# whirlygig.net
KiCad netlist of a schematic drawn in Altium Designer
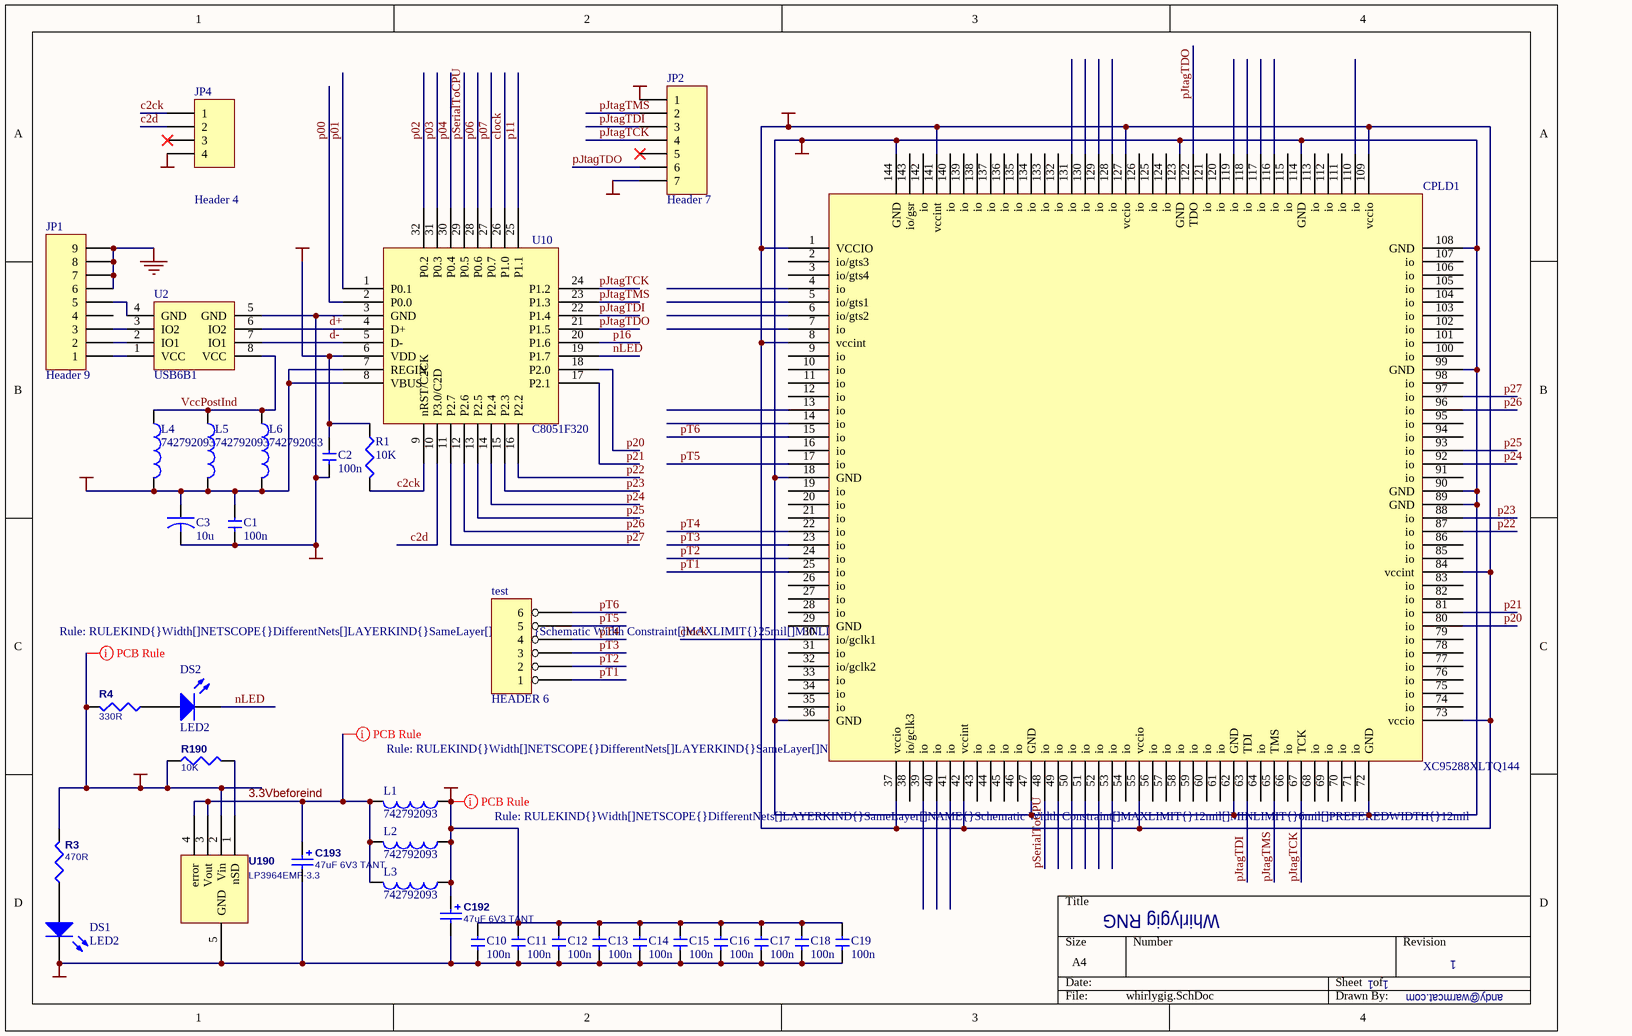
[diagram p0: whirlygig.SchDoc]

(export (version "E")
  (design (tool "Eeschema 10.0.6"))
  (components
    (comp (ref "C1") (value "100n") (footprint "C0603") (libsource (lib "*") (part "100N DISK")))
    (comp (ref "C2") (value "100n") (footprint "C0603") (libsource (lib "*") (part "100N DISK")))
    (comp (ref "C3") (value "10u") (footprint "TAJ-T") (libsource (lib "*") (part "1UF TANT")))
    (comp (ref "C10") (value "100n") (footprint "C0603") (libsource (lib "*") (part "100N DISK")))
    (comp (ref "C11") (value "100n") (footprint "C0603") (libsource (lib "*") (part "100N DISK")))
    (comp (ref "C12") (value "100n") (footprint "C0603") (libsource (lib "*") (part "100N DISK")))
    (comp (ref "C13") (value "100n") (footprint "C0603") (libsource (lib "*") (part "100N DISK")))
    (comp (ref "C14") (value "100n") (footprint "C0603") (libsource (lib "*") (part "100N DISK")))
    (comp (ref "C15") (value "100n") (footprint "C0603") (libsource (lib "*") (part "100N DISK")))
    (comp (ref "C16") (value "100n") (footprint "C0603") (libsource (lib "*") (part "100N DISK")))
    (comp (ref "C17") (value "100n") (footprint "C0603") (libsource (lib "*") (part "100N DISK")))
    (comp (ref "C18") (value "100n") (footprint "C0603") (libsource (lib "*") (part "100N DISK")))
    (comp (ref "C19") (value "100n") (footprint "C0603") (libsource (lib "*") (part "100N DISK")))
    (comp (ref "C192")
      (value "47uF 6V3 TANT")
      (footprint "TAJ-T")
      (description "Polarized Capacitor (Surface Mount)")
      (fields (field (name "PUBLISHER") "Altium Limited"))
      (libsource (lib "Miscellaneous Devices") (part "Cap Pol3"))
    )
    (comp (ref "C193")
      (value "47uF 6V3 TANT")
      (footprint "TAJ-T")
      (description "Polarized Capacitor (Surface Mount)")
      (fields (field (name "PUBLISHER") "Altium Limited"))
      (libsource (lib "Miscellaneous Devices") (part "Cap Pol3"))
    )
    (comp (ref "CPLD1")
      (value "XC95288XLTQ144")
      (footprint "TQFP144")
      (libsource (lib "*") (part "XC95288XLTQ144"))
    )
    (comp (ref "DS1")
      (value "LED2")
      (footprint "DSO-F2/D6.1")
      (description "Typical RED, GREEN, YELLOW, AMBER GaAs LED")
      (fields (field (name "PUBLISHER") "Altium Limited"))
      (libsource (lib "Miscellaneous Devices") (part "LED2"))
    )
    (comp (ref "DS2")
      (value "LED2")
      (footprint "DSO-F2/D6.1")
      (description "Typical RED, GREEN, YELLOW, AMBER GaAs LED")
      (fields (field (name "PUBLISHER") "Altium Limited"))
      (libsource (lib "Miscellaneous Devices") (part "LED2"))
    )
    (comp (ref "JP1")
      (value "Header 9")
      (footprint "USBSKT5MIN")
      (description "Header, 9-Pin")
      (fields (field (name "PUBLISHER") "Altium Limited"))
      (libsource (lib "Miscellaneous Connectors") (part "Header 9"))
    )
    (comp (ref "JP2")
      (value "Header 7")
      (footprint "HDR1X7")
      (description "Header, 7-Pin")
      (fields (field (name "PUBLISHER") "Altium Limited"))
      (libsource (lib "Miscellaneous Connectors") (part "Header 7"))
    )
    (comp (ref "JP4")
      (value "Header 4")
      (footprint "HDR1X4")
      (description "Header, 4-Pin")
      (fields (field (name "PUBLISHER") "Altium Limited"))
      (libsource (lib "Miscellaneous Connectors") (part "Header 4"))
    )
    (comp (ref "L1")
      (value "742792093")
      (footprint "C0805")
      (description "Inductor")
      (fields (field (name "PUBLISHER") "Altium Limited"))
      (libsource (lib "Miscellaneous Devices") (part "Inductor"))
    )
    (comp (ref "L2")
      (value "742792093")
      (footprint "C0805")
      (description "Inductor")
      (fields (field (name "PUBLISHER") "Altium Limited"))
      (libsource (lib "Miscellaneous Devices") (part "Inductor"))
    )
    (comp (ref "L3")
      (value "742792093")
      (footprint "C0805")
      (description "Inductor")
      (fields (field (name "PUBLISHER") "Altium Limited"))
      (libsource (lib "Miscellaneous Devices") (part "Inductor"))
    )
    (comp (ref "L4")
      (value "742792093")
      (footprint "C0805")
      (description "Inductor")
      (fields (field (name "PUBLISHER") "Altium Limited"))
      (libsource (lib "Miscellaneous Devices") (part "Inductor"))
    )
    (comp (ref "L5")
      (value "742792093")
      (footprint "C0805")
      (description "Inductor")
      (fields (field (name "PUBLISHER") "Altium Limited"))
      (libsource (lib "Miscellaneous Devices") (part "Inductor"))
    )
    (comp (ref "L6")
      (value "742792093")
      (footprint "C0805")
      (description "Inductor")
      (fields (field (name "PUBLISHER") "Altium Limited"))
      (libsource (lib "Miscellaneous Devices") (part "Inductor"))
    )
    (comp (ref "R1")
      (value "10K")
      (footprint "R0603")
      (description "Resistor")
      (libsource (lib "*") (part "100K"))
    )
    (comp (ref "R3")
      (value "470R")
      (footprint "R0603")
      (description "Resistor")
      (fields (field (name "PUBLISHER") "Altium Limited"))
      (libsource (lib "") (part "Res3_1"))
    )
    (comp (ref "R4")
      (value "330R")
      (footprint "R0603")
      (description "Resistor")
      (fields (field (name "PUBLISHER") "Altium Limited"))
      (libsource (lib "linuxboard_1") (part "Res3"))
    )
    (comp (ref "R190")
      (value "10K")
      (footprint "R0603")
      (description "Resistor")
      (fields (field (name "PUBLISHER") "Altium Limited"))
      (libsource (lib "linuxboard_1") (part "Res3"))
    )
    (comp (ref "test") (value "HEADER 6") (footprint "HDR1X6") (libsource (lib "*") (part "HEADER 6")))
    (comp (ref "U2")
      (value "USB6B1")
      (footprint "SOP8USB")
      (description "USB Protection Diodes")
      (libsource (lib "*") (part "USB6B1"))
    )
    (comp (ref "U10")
      (value "C8051F320")
      (footprint "LQFP32")
      (description "Cygnal USB flash chip")
      (libsource (lib "*") (part "Component_3"))
    )
    (comp (ref "U190") (value "LP3964EMP-3.3") (footprint "SOT-223-5") (libsource (lib "*") (part "LP3964")))
  )
  (nets
    (net (code "1") (name "/3.3Vbeforeind") (class "Default")
      (node (ref "C193") (pin "1") (pinfunction "1_1") (pintype "passive"))
      (node (ref "L1") (pin "2") (pinfunction "2_2") (pintype "passive"))
      (node (ref "L2") (pin "2") (pinfunction "2_2") (pintype "passive"))
      (node (ref "L3") (pin "2") (pinfunction "2_2") (pintype "passive"))
      (node (ref "U190") (pin "3") (pinfunction "Vout_3") (pintype "passive"))
      (node (ref "U190") (pin "4") (pinfunction "error_4") (pintype "passive"))
    )
    (net (code "2") (name "/VccPostInd") (class "Default")
      (node (ref "L4") (pin "1") (pinfunction "1_1") (pintype "passive"))
      (node (ref "L5") (pin "1") (pinfunction "1_1") (pintype "passive"))
      (node (ref "L6") (pin "1") (pinfunction "1_1") (pintype "passive"))
      (node (ref "U2") (pin "8") (pinfunction "VCC_8") (pintype "passive"))
    )
    (net (code "3") (name "/c2ck") (class "Default")
      (node (ref "JP4") (pin "1") (pinfunction "1_1") (pintype "passive"))
      (node (ref "R1") (pin "2") (pinfunction "2_2") (pintype "passive"))
      (node (ref "U10") (pin "9") (pinfunction "nRST/C2CK_9") (pintype "passive"))
    )
    (net (code "4") (name "/c2d") (class "Default")
      (node (ref "JP4") (pin "2") (pinfunction "2_2") (pintype "passive"))
      (node (ref "U10") (pin "10") (pinfunction "P3.0/C2D_10") (pintype "passive"))
    )
    (net (code "5") (name "/clock") (class "Default")
      (node (ref "CPLD1") (pin "30") (pinfunction "io/gclk1_30") (pintype "passive"))
      (node (ref "U10") (pin "26") (pinfunction "P1.0_26") (pintype "passive"))
    )
    (net (code "6") (name "/d+") (class "Default")
      (node (ref "U10") (pin "4") (pinfunction "D+_4") (pintype "passive"))
      (node (ref "U2") (pin "6") (pinfunction "IO2_6") (pintype "passive"))
    )
    (net (code "7") (name "/d-") (class "Default")
      (node (ref "U10") (pin "5") (pinfunction "D-_5") (pintype "passive"))
      (node (ref "U2") (pin "7") (pinfunction "IO1_7") (pintype "passive"))
    )
    (net (code "8") (name "/nLED") (class "Default")
      (node (ref "DS2") (pin "2") (pinfunction "K_2") (pintype "passive"))
      (node (ref "U10") (pin "19") (pinfunction "P1.7_19") (pintype "passive"))
    )
    (net (code "9") (name "/p00") (class "Default")
      (node (ref "U10") (pin "2") (pinfunction "P0.0_2") (pintype "passive"))
    )
    (net (code "10") (name "/p01") (class "Default")
      (node (ref "U10") (pin "1") (pinfunction "P0.1_1") (pintype "passive"))
    )
    (net (code "11") (name "/p02") (class "Default")
      (node (ref "U10") (pin "32") (pinfunction "P0.2_32") (pintype "passive"))
    )
    (net (code "12") (name "/p03") (class "Default")
      (node (ref "U10") (pin "31") (pinfunction "P0.3_31") (pintype "passive"))
    )
    (net (code "13") (name "/p04") (class "Default")
      (node (ref "U10") (pin "30") (pinfunction "P0.4_30") (pintype "passive"))
    )
    (net (code "14") (name "/p06") (class "Default")
      (node (ref "U10") (pin "28") (pinfunction "P0.6_28") (pintype "passive"))
    )
    (net (code "15") (name "/p07") (class "Default")
      (node (ref "U10") (pin "27") (pinfunction "P0.7_27") (pintype "passive"))
    )
    (net (code "16") (name "/p11") (class "Default")
      (node (ref "U10") (pin "25") (pinfunction "P1.1_25") (pintype "passive"))
    )
    (net (code "17") (name "/p16") (class "Default")
      (node (ref "U10") (pin "20") (pinfunction "P1.6_20") (pintype "passive"))
    )
    (net (code "18") (name "/p20") (class "Default")
      (node (ref "CPLD1") (pin "80") (pinfunction "io_80") (pintype "passive"))
      (node (ref "U10") (pin "18") (pinfunction "P2.0_18") (pintype "passive"))
    )
    (net (code "19") (name "/p21") (class "Default")
      (node (ref "CPLD1") (pin "81") (pinfunction "io_81") (pintype "passive"))
      (node (ref "U10") (pin "17") (pinfunction "P2.1_17") (pintype "passive"))
    )
    (net (code "20") (name "/p22") (class "Default")
      (node (ref "CPLD1") (pin "87") (pinfunction "io_87") (pintype "passive"))
      (node (ref "U10") (pin "16") (pinfunction "P2.2_16") (pintype "passive"))
    )
    (net (code "21") (name "/p23") (class "Default")
      (node (ref "CPLD1") (pin "88") (pinfunction "io_88") (pintype "passive"))
      (node (ref "U10") (pin "15") (pinfunction "P2.3_15") (pintype "passive"))
    )
    (net (code "22") (name "/p24") (class "Default")
      (node (ref "CPLD1") (pin "92") (pinfunction "io_92") (pintype "passive"))
      (node (ref "U10") (pin "14") (pinfunction "P2.4_14") (pintype "passive"))
    )
    (net (code "23") (name "/p25") (class "Default")
      (node (ref "CPLD1") (pin "93") (pinfunction "io_93") (pintype "passive"))
      (node (ref "U10") (pin "13") (pinfunction "P2.5_13") (pintype "passive"))
    )
    (net (code "24") (name "/p26") (class "Default")
      (node (ref "CPLD1") (pin "96") (pinfunction "io_96") (pintype "passive"))
      (node (ref "U10") (pin "12") (pinfunction "P2.6_12") (pintype "passive"))
    )
    (net (code "25") (name "/p27") (class "Default")
      (node (ref "CPLD1") (pin "97") (pinfunction "io_97") (pintype "passive"))
      (node (ref "U10") (pin "11") (pinfunction "P2.7_11") (pintype "passive"))
    )
    (net (code "26") (name "/pJtagTCK") (class "Default")
      (node (ref "CPLD1") (pin "67") (pinfunction "TCK_67") (pintype "passive"))
      (node (ref "JP2") (pin "4") (pinfunction "4_4") (pintype "passive"))
      (node (ref "U10") (pin "24") (pinfunction "P1.2_24") (pintype "passive"))
    )
    (net (code "27") (name "/pJtagTDI") (class "Default")
      (node (ref "CPLD1") (pin "63") (pinfunction "TDI_63") (pintype "passive"))
      (node (ref "JP2") (pin "3") (pinfunction "3_3") (pintype "passive"))
      (node (ref "U10") (pin "22") (pinfunction "P1.4_22") (pintype "passive"))
    )
    (net (code "28") (name "/pJtagTDO") (class "Default")
      (node (ref "CPLD1") (pin "122") (pinfunction "TDO_122") (pintype "passive"))
      (node (ref "JP2") (pin "6") (pinfunction "6_6") (pintype "passive"))
      (node (ref "U10") (pin "21") (pinfunction "P1.5_21") (pintype "passive"))
    )
    (net (code "29") (name "/pJtagTMS") (class "Default")
      (node (ref "CPLD1") (pin "65") (pinfunction "TMS_65") (pintype "passive"))
      (node (ref "JP2") (pin "2") (pinfunction "2_2") (pintype "passive"))
      (node (ref "U10") (pin "23") (pinfunction "P1.3_23") (pintype "passive"))
    )
    (net (code "30") (name "/pSerialToCPU") (class "Default")
      (node (ref "CPLD1") (pin "48") (pinfunction "io_48") (pintype "passive"))
      (node (ref "U10") (pin "29") (pinfunction "P0.5_29") (pintype "passive"))
    )
    (net (code "31") (name "/pT1") (class "Default")
      (node (ref "CPLD1") (pin "25") (pinfunction "io_25") (pintype "passive"))
      (node (ref "test") (pin "1") (pinfunction "1_1") (pintype "passive"))
    )
    (net (code "32") (name "/pT2") (class "Default")
      (node (ref "CPLD1") (pin "24") (pinfunction "io_24") (pintype "passive"))
      (node (ref "test") (pin "2") (pinfunction "2_2") (pintype "passive"))
    )
    (net (code "33") (name "/pT3") (class "Default")
      (node (ref "CPLD1") (pin "23") (pinfunction "io_23") (pintype "passive"))
      (node (ref "test") (pin "3") (pinfunction "3_3") (pintype "passive"))
    )
    (net (code "34") (name "/pT4") (class "Default")
      (node (ref "CPLD1") (pin "22") (pinfunction "io_22") (pintype "passive"))
      (node (ref "test") (pin "4") (pinfunction "4_4") (pintype "passive"))
    )
    (net (code "35") (name "/pT5") (class "Default")
      (node (ref "CPLD1") (pin "17") (pinfunction "io_17") (pintype "passive"))
      (node (ref "test") (pin "5") (pinfunction "5_5") (pintype "passive"))
    )
    (net (code "36") (name "/pT6") (class "Default")
      (node (ref "CPLD1") (pin "15") (pinfunction "io_15") (pintype "passive"))
      (node (ref "test") (pin "6") (pinfunction "6_6") (pintype "passive"))
    )
    (net (code "37") (name "3.3V") (class "Default")
      (node (ref "C10") (pin "1") (pinfunction "1_1") (pintype "passive"))
      (node (ref "C11") (pin "1") (pinfunction "1_1") (pintype "passive"))
      (node (ref "C12") (pin "1") (pinfunction "1_1") (pintype "passive"))
      (node (ref "C13") (pin "1") (pinfunction "1_1") (pintype "passive"))
      (node (ref "C14") (pin "1") (pinfunction "1_1") (pintype "passive"))
      (node (ref "C15") (pin "1") (pinfunction "1_1") (pintype "passive"))
      (node (ref "C16") (pin "1") (pinfunction "1_1") (pintype "passive"))
      (node (ref "C17") (pin "1") (pinfunction "1_1") (pintype "passive"))
      (node (ref "C18") (pin "1") (pinfunction "1_1") (pintype "passive"))
      (node (ref "C19") (pin "1") (pinfunction "1_1") (pintype "passive"))
      (node (ref "C192") (pin "1") (pinfunction "1_1") (pintype "passive"))
      (node (ref "CPLD1") (pin "1") (pinfunction "VCCIO_1") (pintype "passive"))
      (node (ref "CPLD1") (pin "109") (pinfunction "vccio_109") (pintype "passive"))
      (node (ref "CPLD1") (pin "127") (pinfunction "vccio_127") (pintype "passive"))
      (node (ref "CPLD1") (pin "141") (pinfunction "vccint_141") (pintype "passive"))
      (node (ref "CPLD1") (pin "37") (pinfunction "vccio_37") (pintype "passive"))
      (node (ref "CPLD1") (pin "42") (pinfunction "vccint_42") (pintype "passive"))
      (node (ref "CPLD1") (pin "55") (pinfunction "vccio_55") (pintype "passive"))
      (node (ref "CPLD1") (pin "73") (pinfunction "vccio_73") (pintype "passive"))
      (node (ref "CPLD1") (pin "8") (pinfunction "vccint_8") (pintype "passive"))
      (node (ref "CPLD1") (pin "84") (pinfunction "vccint_84") (pintype "passive"))
      (node (ref "JP2") (pin "1") (pinfunction "1_1") (pintype "passive"))
      (node (ref "L1") (pin "1") (pinfunction "1_1") (pintype "passive"))
      (node (ref "L2") (pin "1") (pinfunction "1_1") (pintype "passive"))
      (node (ref "L3") (pin "1") (pinfunction "1_1") (pintype "passive"))
    )
    (net (code "38") (name "3V") (class "Default")
      (node (ref "C2") (pin "1") (pinfunction "1_1") (pintype "passive"))
      (node (ref "R1") (pin "1") (pinfunction "1_1") (pintype "passive"))
      (node (ref "U10") (pin "6") (pinfunction "VDD_6") (pintype "passive"))
    )
    (net (code "39") (name "GND") (class "Default")
      (node (ref "C1") (pin "2") (pinfunction "2_2") (pintype "passive"))
      (node (ref "C10") (pin "2") (pinfunction "2_2") (pintype "passive"))
      (node (ref "C11") (pin "2") (pinfunction "2_2") (pintype "passive"))
      (node (ref "C12") (pin "2") (pinfunction "2_2") (pintype "passive"))
      (node (ref "C13") (pin "2") (pinfunction "2_2") (pintype "passive"))
      (node (ref "C14") (pin "2") (pinfunction "2_2") (pintype "passive"))
      (node (ref "C15") (pin "2") (pinfunction "2_2") (pintype "passive"))
      (node (ref "C16") (pin "2") (pinfunction "2_2") (pintype "passive"))
      (node (ref "C17") (pin "2") (pinfunction "2_2") (pintype "passive"))
      (node (ref "C18") (pin "2") (pinfunction "2_2") (pintype "passive"))
      (node (ref "C19") (pin "2") (pinfunction "2_2") (pintype "passive"))
      (node (ref "C192") (pin "2") (pinfunction "2_2") (pintype "passive"))
      (node (ref "C193") (pin "2") (pinfunction "2_2") (pintype "passive"))
      (node (ref "C2") (pin "2") (pinfunction "2_2") (pintype "passive"))
      (node (ref "C3") (pin "2") (pinfunction "2_2") (pintype "passive"))
      (node (ref "CPLD1") (pin "108") (pinfunction "GND_108") (pintype "passive"))
      (node (ref "CPLD1") (pin "114") (pinfunction "GND_114") (pintype "passive"))
      (node (ref "CPLD1") (pin "123") (pinfunction "GND_123") (pintype "passive"))
      (node (ref "CPLD1") (pin "144") (pinfunction "GND_144") (pintype "passive"))
      (node (ref "CPLD1") (pin "18") (pinfunction "GND_18") (pintype "passive"))
      (node (ref "CPLD1") (pin "36") (pinfunction "GND_36") (pintype "passive"))
      (node (ref "CPLD1") (pin "47") (pinfunction "GND_47") (pintype "passive"))
      (node (ref "CPLD1") (pin "62") (pinfunction "GND_62") (pintype "passive"))
      (node (ref "CPLD1") (pin "72") (pinfunction "GND_72") (pintype "passive"))
      (node (ref "CPLD1") (pin "89") (pinfunction "GND_89") (pintype "passive"))
      (node (ref "CPLD1") (pin "90") (pinfunction "GND_90") (pintype "passive"))
      (node (ref "CPLD1") (pin "99") (pinfunction "GND_99") (pintype "passive"))
      (node (ref "DS1") (pin "2") (pinfunction "K_2") (pintype "passive"))
      (node (ref "JP2") (pin "7") (pinfunction "7_7") (pintype "passive"))
      (node (ref "JP4") (pin "4") (pinfunction "4_4") (pintype "passive"))
      (node (ref "U10") (pin "3") (pinfunction "GND_3") (pintype "passive"))
      (node (ref "U190") (pin "5") (pinfunction "GND_5") (pintype "passive"))
      (node (ref "U2") (pin "5") (pinfunction "GND_5") (pintype "passive"))
    )
    (net (code "40") (name "Net-(DS1-A)") (class "Default")
      (node (ref "DS1") (pin "1") (pinfunction "A_1") (pintype "passive"))
      (node (ref "R3") (pin "2") (pinfunction "2_2") (pintype "passive"))
    )
    (net (code "41") (name "Net-(DS2-A)") (class "Default")
      (node (ref "DS2") (pin "1") (pinfunction "A_1") (pintype "passive"))
      (node (ref "R4") (pin "2") (pinfunction "2_2") (pintype "passive"))
    )
    (net (code "42") (name "Net-(JP1-Pad1)") (class "Default")
      (node (ref "JP1") (pin "1") (pinfunction "1_1") (pintype "passive"))
      (node (ref "U2") (pin "1") (pinfunction "VCC_1") (pintype "passive"))
    )
    (net (code "43") (name "Net-(JP1-Pad2)") (class "Default")
      (node (ref "JP1") (pin "2") (pinfunction "2_2") (pintype "passive"))
      (node (ref "U2") (pin "2") (pinfunction "IO1_2") (pintype "passive"))
    )
    (net (code "44") (name "Net-(JP1-Pad3)") (class "Default")
      (node (ref "JP1") (pin "3") (pinfunction "3_3") (pintype "passive"))
      (node (ref "U2") (pin "3") (pinfunction "IO2_3") (pintype "passive"))
    )
    (net (code "45") (name "Net-(JP1-Pad5)") (class "Default")
      (node (ref "JP1") (pin "5") (pinfunction "5_5") (pintype "passive"))
      (node (ref "U2") (pin "4") (pinfunction "GND_4") (pintype "passive"))
    )
    (net (code "46") (name "Net-(U190-nSD)") (class "Default")
      (node (ref "R190") (pin "1") (pinfunction "1_1") (pintype "passive"))
      (node (ref "U190") (pin "1") (pinfunction "nSD_1") (pintype "passive"))
    )
    (net (code "47") (name "SHIELD") (class "Default")
      (node (ref "JP1") (pin "6") (pinfunction "6_6") (pintype "passive"))
      (node (ref "JP1") (pin "7") (pinfunction "7_7") (pintype "passive"))
      (node (ref "JP1") (pin "8") (pinfunction "8_8") (pintype "passive"))
      (node (ref "JP1") (pin "9") (pinfunction "9_9") (pintype "passive"))
    )
    (net (code "48") (name "VBUSIN") (class "Default")
      (node (ref "C1") (pin "1") (pinfunction "1_1") (pintype "passive"))
      (node (ref "C3") (pin "1") (pinfunction "1_1") (pintype "passive"))
      (node (ref "L4") (pin "2") (pinfunction "2_2") (pintype "passive"))
      (node (ref "L5") (pin "2") (pinfunction "2_2") (pintype "passive"))
      (node (ref "L6") (pin "2") (pinfunction "2_2") (pintype "passive"))
      (node (ref "R190") (pin "2") (pinfunction "2_2") (pintype "passive"))
      (node (ref "R3") (pin "1") (pinfunction "1_1") (pintype "passive"))
      (node (ref "R4") (pin "1") (pinfunction "1_1") (pintype "passive"))
      (node (ref "U10") (pin "7") (pinfunction "REGIN_7") (pintype "passive"))
      (node (ref "U10") (pin "8") (pinfunction "VBUS_8") (pintype "passive"))
      (node (ref "U190") (pin "2") (pinfunction "Vin_2") (pintype "passive"))
    )
    (net (code "49") (name "unconnected-(CPLD1-GND-Pad29)") (class "Default")
      (node (ref "CPLD1") (pin "29") (pinfunction "GND_29") (pintype "passive"))
    )
    (net (code "50") (name "unconnected-(CPLD1-io-Pad4)") (class "Default")
      (node (ref "CPLD1") (pin "4") (pinfunction "io_4") (pintype "passive"))
    )
    (net (code "51") (name "unconnected-(CPLD1-io-Pad7)") (class "Default")
      (node (ref "CPLD1") (pin "7") (pinfunction "io_7") (pintype "passive"))
    )
    (net (code "52") (name "unconnected-(CPLD1-io-Pad9)") (class "Default")
      (node (ref "CPLD1") (pin "9") (pinfunction "io_9") (pintype "passive"))
    )
    (net (code "53") (name "unconnected-(CPLD1-io-Pad10)") (class "Default")
      (node (ref "CPLD1") (pin "10") (pinfunction "io_10") (pintype "passive"))
    )
    (net (code "54") (name "unconnected-(CPLD1-io-Pad11)") (class "Default")
      (node (ref "CPLD1") (pin "11") (pinfunction "io_11") (pintype "passive"))
    )
    (net (code "55") (name "unconnected-(CPLD1-io-Pad12)") (class "Default")
      (node (ref "CPLD1") (pin "12") (pinfunction "io_12") (pintype "passive"))
    )
    (net (code "56") (name "unconnected-(CPLD1-io-Pad13)") (class "Default")
      (node (ref "CPLD1") (pin "13") (pinfunction "io_13") (pintype "passive"))
    )
    (net (code "57") (name "unconnected-(CPLD1-io-Pad14)") (class "Default")
      (node (ref "CPLD1") (pin "14") (pinfunction "io_14") (pintype "passive"))
    )
    (net (code "58") (name "unconnected-(CPLD1-io-Pad16)") (class "Default")
      (node (ref "CPLD1") (pin "16") (pinfunction "io_16") (pintype "passive"))
    )
    (net (code "59") (name "unconnected-(CPLD1-io-Pad19)") (class "Default")
      (node (ref "CPLD1") (pin "19") (pinfunction "io_19") (pintype "passive"))
    )
    (net (code "60") (name "unconnected-(CPLD1-io-Pad20)") (class "Default")
      (node (ref "CPLD1") (pin "20") (pinfunction "io_20") (pintype "passive"))
    )
    (net (code "61") (name "unconnected-(CPLD1-io-Pad21)") (class "Default")
      (node (ref "CPLD1") (pin "21") (pinfunction "io_21") (pintype "passive"))
    )
    (net (code "62") (name "unconnected-(CPLD1-io-Pad26)") (class "Default")
      (node (ref "CPLD1") (pin "26") (pinfunction "io_26") (pintype "passive"))
    )
    (net (code "63") (name "unconnected-(CPLD1-io-Pad27)") (class "Default")
      (node (ref "CPLD1") (pin "27") (pinfunction "io_27") (pintype "passive"))
    )
    (net (code "64") (name "unconnected-(CPLD1-io-Pad28)") (class "Default")
      (node (ref "CPLD1") (pin "28") (pinfunction "io_28") (pintype "passive"))
    )
    (net (code "65") (name "unconnected-(CPLD1-io-Pad31)") (class "Default")
      (node (ref "CPLD1") (pin "31") (pinfunction "io_31") (pintype "passive"))
    )
    (net (code "66") (name "unconnected-(CPLD1-io-Pad33)") (class "Default")
      (node (ref "CPLD1") (pin "33") (pinfunction "io_33") (pintype "passive"))
    )
    (net (code "67") (name "unconnected-(CPLD1-io-Pad34)") (class "Default")
      (node (ref "CPLD1") (pin "34") (pinfunction "io_34") (pintype "passive"))
    )
    (net (code "68") (name "unconnected-(CPLD1-io-Pad35)") (class "Default")
      (node (ref "CPLD1") (pin "35") (pinfunction "io_35") (pintype "passive"))
    )
    (net (code "69") (name "unconnected-(CPLD1-io-Pad39)") (class "Default")
      (node (ref "CPLD1") (pin "39") (pinfunction "io_39") (pintype "passive"))
    )
    (net (code "70") (name "unconnected-(CPLD1-io-Pad40)") (class "Default")
      (node (ref "CPLD1") (pin "40") (pinfunction "io_40") (pintype "passive"))
    )
    (net (code "71") (name "unconnected-(CPLD1-io-Pad41)") (class "Default")
      (node (ref "CPLD1") (pin "41") (pinfunction "io_41") (pintype "passive"))
    )
    (net (code "72") (name "unconnected-(CPLD1-io-Pad43)") (class "Default")
      (node (ref "CPLD1") (pin "43") (pinfunction "io_43") (pintype "passive"))
    )
    (net (code "73") (name "unconnected-(CPLD1-io-Pad44)") (class "Default")
      (node (ref "CPLD1") (pin "44") (pinfunction "io_44") (pintype "passive"))
    )
    (net (code "74") (name "unconnected-(CPLD1-io-Pad45)") (class "Default")
      (node (ref "CPLD1") (pin "45") (pinfunction "io_45") (pintype "passive"))
    )
    (net (code "75") (name "unconnected-(CPLD1-io-Pad46)") (class "Default")
      (node (ref "CPLD1") (pin "46") (pinfunction "io_46") (pintype "passive"))
    )
    (net (code "76") (name "unconnected-(CPLD1-io-Pad49)") (class "Default")
      (node (ref "CPLD1") (pin "49") (pinfunction "io_49") (pintype "passive"))
    )
    (net (code "77") (name "unconnected-(CPLD1-io-Pad50)") (class "Default")
      (node (ref "CPLD1") (pin "50") (pinfunction "io_50") (pintype "passive"))
    )
    (net (code "78") (name "unconnected-(CPLD1-io-Pad51)") (class "Default")
      (node (ref "CPLD1") (pin "51") (pinfunction "io_51") (pintype "passive"))
    )
    (net (code "79") (name "unconnected-(CPLD1-io-Pad52)") (class "Default")
      (node (ref "CPLD1") (pin "52") (pinfunction "io_52") (pintype "passive"))
    )
    (net (code "80") (name "unconnected-(CPLD1-io-Pad53)") (class "Default")
      (node (ref "CPLD1") (pin "53") (pinfunction "io_53") (pintype "passive"))
    )
    (net (code "81") (name "unconnected-(CPLD1-io-Pad54)") (class "Default")
      (node (ref "CPLD1") (pin "54") (pinfunction "io_54") (pintype "passive"))
    )
    (net (code "82") (name "unconnected-(CPLD1-io-Pad56)") (class "Default")
      (node (ref "CPLD1") (pin "56") (pinfunction "io_56") (pintype "passive"))
    )
    (net (code "83") (name "unconnected-(CPLD1-io-Pad57)") (class "Default")
      (node (ref "CPLD1") (pin "57") (pinfunction "io_57") (pintype "passive"))
    )
    (net (code "84") (name "unconnected-(CPLD1-io-Pad58)") (class "Default")
      (node (ref "CPLD1") (pin "58") (pinfunction "io_58") (pintype "passive"))
    )
    (net (code "85") (name "unconnected-(CPLD1-io-Pad59)") (class "Default")
      (node (ref "CPLD1") (pin "59") (pinfunction "io_59") (pintype "passive"))
    )
    (net (code "86") (name "unconnected-(CPLD1-io-Pad60)") (class "Default")
      (node (ref "CPLD1") (pin "60") (pinfunction "io_60") (pintype "passive"))
    )
    (net (code "87") (name "unconnected-(CPLD1-io-Pad61)") (class "Default")
      (node (ref "CPLD1") (pin "61") (pinfunction "io_61") (pintype "passive"))
    )
    (net (code "88") (name "unconnected-(CPLD1-io-Pad64)") (class "Default")
      (node (ref "CPLD1") (pin "64") (pinfunction "io_64") (pintype "passive"))
    )
    (net (code "89") (name "unconnected-(CPLD1-io-Pad66)") (class "Default")
      (node (ref "CPLD1") (pin "66") (pinfunction "io_66") (pintype "passive"))
    )
    (net (code "90") (name "unconnected-(CPLD1-io-Pad68)") (class "Default")
      (node (ref "CPLD1") (pin "68") (pinfunction "io_68") (pintype "passive"))
    )
    (net (code "91") (name "unconnected-(CPLD1-io-Pad69)") (class "Default")
      (node (ref "CPLD1") (pin "69") (pinfunction "io_69") (pintype "passive"))
    )
    (net (code "92") (name "unconnected-(CPLD1-io-Pad70)") (class "Default")
      (node (ref "CPLD1") (pin "70") (pinfunction "io_70") (pintype "passive"))
    )
    (net (code "93") (name "unconnected-(CPLD1-io-Pad71)") (class "Default")
      (node (ref "CPLD1") (pin "71") (pinfunction "io_71") (pintype "passive"))
    )
    (net (code "94") (name "unconnected-(CPLD1-io-Pad74)") (class "Default")
      (node (ref "CPLD1") (pin "74") (pinfunction "io_74") (pintype "passive"))
    )
    (net (code "95") (name "unconnected-(CPLD1-io-Pad75)") (class "Default")
      (node (ref "CPLD1") (pin "75") (pinfunction "io_75") (pintype "passive"))
    )
    (net (code "96") (name "unconnected-(CPLD1-io-Pad76)") (class "Default")
      (node (ref "CPLD1") (pin "76") (pinfunction "io_76") (pintype "passive"))
    )
    (net (code "97") (name "unconnected-(CPLD1-io-Pad77)") (class "Default")
      (node (ref "CPLD1") (pin "77") (pinfunction "io_77") (pintype "passive"))
    )
    (net (code "98") (name "unconnected-(CPLD1-io-Pad78)") (class "Default")
      (node (ref "CPLD1") (pin "78") (pinfunction "io_78") (pintype "passive"))
    )
    (net (code "99") (name "unconnected-(CPLD1-io-Pad79)") (class "Default")
      (node (ref "CPLD1") (pin "79") (pinfunction "io_79") (pintype "passive"))
    )
    (net (code "100") (name "unconnected-(CPLD1-io-Pad82)") (class "Default")
      (node (ref "CPLD1") (pin "82") (pinfunction "io_82") (pintype "passive"))
    )
    (net (code "101") (name "unconnected-(CPLD1-io-Pad83)") (class "Default")
      (node (ref "CPLD1") (pin "83") (pinfunction "io_83") (pintype "passive"))
    )
    (net (code "102") (name "unconnected-(CPLD1-io-Pad85)") (class "Default")
      (node (ref "CPLD1") (pin "85") (pinfunction "io_85") (pintype "passive"))
    )
    (net (code "103") (name "unconnected-(CPLD1-io-Pad86)") (class "Default")
      (node (ref "CPLD1") (pin "86") (pinfunction "io_86") (pintype "passive"))
    )
    (net (code "104") (name "unconnected-(CPLD1-io-Pad91)") (class "Default")
      (node (ref "CPLD1") (pin "91") (pinfunction "io_91") (pintype "passive"))
    )
    (net (code "105") (name "unconnected-(CPLD1-io-Pad94)") (class "Default")
      (node (ref "CPLD1") (pin "94") (pinfunction "io_94") (pintype "passive"))
    )
    (net (code "106") (name "unconnected-(CPLD1-io-Pad95)") (class "Default")
      (node (ref "CPLD1") (pin "95") (pinfunction "io_95") (pintype "passive"))
    )
    (net (code "107") (name "unconnected-(CPLD1-io-Pad98)") (class "Default")
      (node (ref "CPLD1") (pin "98") (pinfunction "io_98") (pintype "passive"))
    )
    (net (code "108") (name "unconnected-(CPLD1-io-Pad100)") (class "Default")
      (node (ref "CPLD1") (pin "100") (pinfunction "io_100") (pintype "passive"))
    )
    (net (code "109") (name "unconnected-(CPLD1-io-Pad101)") (class "Default")
      (node (ref "CPLD1") (pin "101") (pinfunction "io_101") (pintype "passive"))
    )
    (net (code "110") (name "unconnected-(CPLD1-io-Pad102)") (class "Default")
      (node (ref "CPLD1") (pin "102") (pinfunction "io_102") (pintype "passive"))
    )
    (net (code "111") (name "unconnected-(CPLD1-io-Pad103)") (class "Default")
      (node (ref "CPLD1") (pin "103") (pinfunction "io_103") (pintype "passive"))
    )
    (net (code "112") (name "unconnected-(CPLD1-io-Pad104)") (class "Default")
      (node (ref "CPLD1") (pin "104") (pinfunction "io_104") (pintype "passive"))
    )
    (net (code "113") (name "unconnected-(CPLD1-io-Pad105)") (class "Default")
      (node (ref "CPLD1") (pin "105") (pinfunction "io_105") (pintype "passive"))
    )
    (net (code "114") (name "unconnected-(CPLD1-io-Pad106)") (class "Default")
      (node (ref "CPLD1") (pin "106") (pinfunction "io_106") (pintype "passive"))
    )
    (net (code "115") (name "unconnected-(CPLD1-io-Pad107)") (class "Default")
      (node (ref "CPLD1") (pin "107") (pinfunction "io_107") (pintype "passive"))
    )
    (net (code "116") (name "unconnected-(CPLD1-io-Pad110)") (class "Default")
      (node (ref "CPLD1") (pin "110") (pinfunction "io_110") (pintype "passive"))
    )
    (net (code "117") (name "unconnected-(CPLD1-io-Pad111)") (class "Default")
      (node (ref "CPLD1") (pin "111") (pinfunction "io_111") (pintype "passive"))
    )
    (net (code "118") (name "unconnected-(CPLD1-io-Pad112)") (class "Default")
      (node (ref "CPLD1") (pin "112") (pinfunction "io_112") (pintype "passive"))
    )
    (net (code "119") (name "unconnected-(CPLD1-io-Pad113)") (class "Default")
      (node (ref "CPLD1") (pin "113") (pinfunction "io_113") (pintype "passive"))
    )
    (net (code "120") (name "unconnected-(CPLD1-io-Pad115)") (class "Default")
      (node (ref "CPLD1") (pin "115") (pinfunction "io_115") (pintype "passive"))
    )
    (net (code "121") (name "unconnected-(CPLD1-io-Pad116)") (class "Default")
      (node (ref "CPLD1") (pin "116") (pinfunction "io_116") (pintype "passive"))
    )
    (net (code "122") (name "unconnected-(CPLD1-io-Pad117)") (class "Default")
      (node (ref "CPLD1") (pin "117") (pinfunction "io_117") (pintype "passive"))
    )
    (net (code "123") (name "unconnected-(CPLD1-io-Pad118)") (class "Default")
      (node (ref "CPLD1") (pin "118") (pinfunction "io_118") (pintype "passive"))
    )
    (net (code "124") (name "unconnected-(CPLD1-io-Pad119)") (class "Default")
      (node (ref "CPLD1") (pin "119") (pinfunction "io_119") (pintype "passive"))
    )
    (net (code "125") (name "unconnected-(CPLD1-io-Pad120)") (class "Default")
      (node (ref "CPLD1") (pin "120") (pinfunction "io_120") (pintype "passive"))
    )
    (net (code "126") (name "unconnected-(CPLD1-io-Pad121)") (class "Default")
      (node (ref "CPLD1") (pin "121") (pinfunction "io_121") (pintype "passive"))
    )
    (net (code "127") (name "unconnected-(CPLD1-io-Pad124)") (class "Default")
      (node (ref "CPLD1") (pin "124") (pinfunction "io_124") (pintype "passive"))
    )
    (net (code "128") (name "unconnected-(CPLD1-io-Pad125)") (class "Default")
      (node (ref "CPLD1") (pin "125") (pinfunction "io_125") (pintype "passive"))
    )
    (net (code "129") (name "unconnected-(CPLD1-io-Pad126)") (class "Default")
      (node (ref "CPLD1") (pin "126") (pinfunction "io_126") (pintype "passive"))
    )
    (net (code "130") (name "unconnected-(CPLD1-io-Pad128)") (class "Default")
      (node (ref "CPLD1") (pin "128") (pinfunction "io_128") (pintype "passive"))
    )
    (net (code "131") (name "unconnected-(CPLD1-io-Pad129)") (class "Default")
      (node (ref "CPLD1") (pin "129") (pinfunction "io_129") (pintype "passive"))
    )
    (net (code "132") (name "unconnected-(CPLD1-io-Pad130)") (class "Default")
      (node (ref "CPLD1") (pin "130") (pinfunction "io_130") (pintype "passive"))
    )
    (net (code "133") (name "unconnected-(CPLD1-io-Pad131)") (class "Default")
      (node (ref "CPLD1") (pin "131") (pinfunction "io_131") (pintype "passive"))
    )
    (net (code "134") (name "unconnected-(CPLD1-io-Pad132)") (class "Default")
      (node (ref "CPLD1") (pin "132") (pinfunction "io_132") (pintype "passive"))
    )
    (net (code "135") (name "unconnected-(CPLD1-io-Pad133)") (class "Default")
      (node (ref "CPLD1") (pin "133") (pinfunction "io_133") (pintype "passive"))
    )
    (net (code "136") (name "unconnected-(CPLD1-io-Pad134)") (class "Default")
      (node (ref "CPLD1") (pin "134") (pinfunction "io_134") (pintype "passive"))
    )
    (net (code "137") (name "unconnected-(CPLD1-io-Pad135)") (class "Default")
      (node (ref "CPLD1") (pin "135") (pinfunction "io_135") (pintype "passive"))
    )
    (net (code "138") (name "unconnected-(CPLD1-io-Pad136)") (class "Default")
      (node (ref "CPLD1") (pin "136") (pinfunction "io_136") (pintype "passive"))
    )
    (net (code "139") (name "unconnected-(CPLD1-io-Pad137)") (class "Default")
      (node (ref "CPLD1") (pin "137") (pinfunction "io_137") (pintype "passive"))
    )
    (net (code "140") (name "unconnected-(CPLD1-io-Pad138)") (class "Default")
      (node (ref "CPLD1") (pin "138") (pinfunction "io_138") (pintype "passive"))
    )
    (net (code "141") (name "unconnected-(CPLD1-io-Pad139)") (class "Default")
      (node (ref "CPLD1") (pin "139") (pinfunction "io_139") (pintype "passive"))
    )
    (net (code "142") (name "unconnected-(CPLD1-io-Pad140)") (class "Default")
      (node (ref "CPLD1") (pin "140") (pinfunction "io_140") (pintype "passive"))
    )
    (net (code "143") (name "unconnected-(CPLD1-io-Pad142)") (class "Default")
      (node (ref "CPLD1") (pin "142") (pinfunction "io_142") (pintype "passive"))
    )
    (net (code "144") (name "unconnected-(CPLD1-io{slash}gclk2-Pad32)") (class "Default")
      (node (ref "CPLD1") (pin "32") (pinfunction "io/gclk2_32") (pintype "passive"))
    )
    (net (code "145") (name "unconnected-(CPLD1-io{slash}gclk3-Pad38)") (class "Default")
      (node (ref "CPLD1") (pin "38") (pinfunction "io/gclk3_38") (pintype "passive"))
    )
    (net (code "146") (name "unconnected-(CPLD1-io{slash}gsr-Pad143)") (class "Default")
      (node (ref "CPLD1") (pin "143") (pinfunction "io/gsr_143") (pintype "passive"))
    )
    (net (code "147") (name "unconnected-(CPLD1-io{slash}gts1-Pad5)") (class "Default")
      (node (ref "CPLD1") (pin "5") (pinfunction "io/gts1_5") (pintype "passive"))
    )
    (net (code "148") (name "unconnected-(CPLD1-io{slash}gts2-Pad6)") (class "Default")
      (node (ref "CPLD1") (pin "6") (pinfunction "io/gts2_6") (pintype "passive"))
    )
    (net (code "149") (name "unconnected-(CPLD1-io{slash}gts3-Pad2)") (class "Default")
      (node (ref "CPLD1") (pin "2") (pinfunction "io/gts3_2") (pintype "passive"))
    )
    (net (code "150") (name "unconnected-(CPLD1-io{slash}gts4-Pad3)") (class "Default")
      (node (ref "CPLD1") (pin "3") (pinfunction "io/gts4_3") (pintype "passive"))
    )
    (net (code "151") (name "unconnected-(JP1-Pad4)") (class "Default")
      (node (ref "JP1") (pin "4") (pinfunction "4_4") (pintype "passive"))
    )
    (net (code "152") (name "unconnected-(JP2-Pad5)") (class "Default")
      (node (ref "JP2") (pin "5") (pinfunction "5_5") (pintype "passive+no_connect"))
    )
    (net (code "153") (name "unconnected-(JP4-Pad3)") (class "Default")
      (node (ref "JP4") (pin "3") (pinfunction "3_3") (pintype "passive+no_connect"))
    )
  )
)
